# 360_led_stick_3_layer.net
KiCad netlist of a schematic drawn in EAGLE
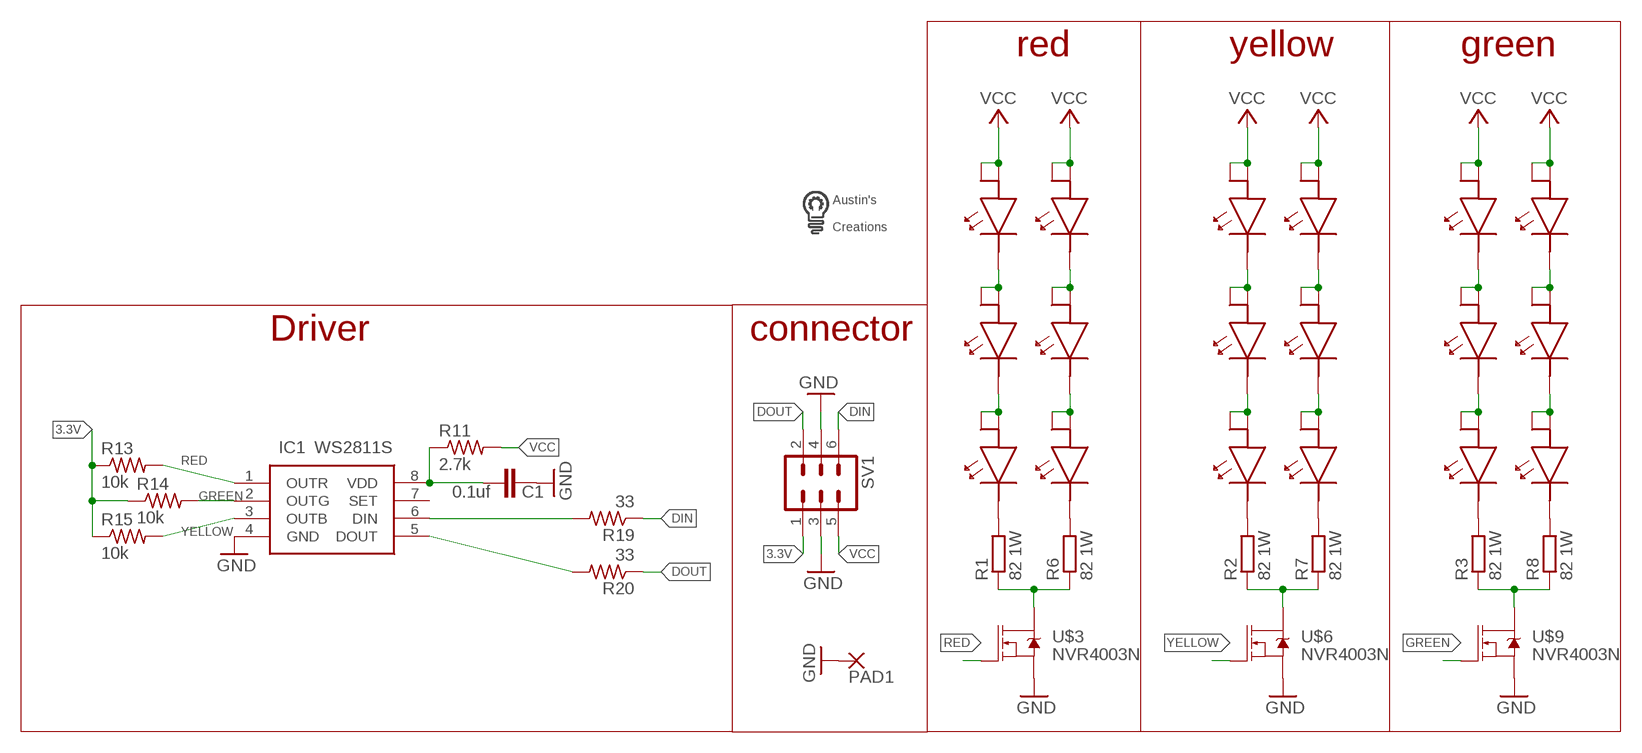
[diagram p0: schematic, sheet 1]

(export (version "E")
  (design (tool "Eeschema 10.0.6"))
  (components
    (comp (ref "C1")
      (value "0.1uf")
      (footprint "eagle-import:C0603K")
      (libsource (lib "eagle-import") (part "C-EUC0603K"))
    )
    (comp (ref "IC1")
      (value "WS2811S")
      (footprint "eagle-import:SOIC127P600X175-8N")
      (fields (field (name "MANUFACTURER_PART_NUMBER") "ws2811s"))
      (libsource (lib "eagle-import") (part "WS2811S"))
    )
    (comp (ref "PAD1")
      (value "WIREPADSMD1,27-254")
      (footprint "eagle-import:SMD1,27-2,54")
      (libsource (lib "eagle-import") (part "WIREPADSMD1,27-254"))
    )
    (comp (ref "R1")
      (value "82 1W")
      (footprint "eagle-import:R1210")
      (libsource (lib "eagle-import") (part "R-EU_R1210"))
    )
    (comp (ref "R2")
      (value "82 1W")
      (footprint "eagle-import:R1210")
      (libsource (lib "eagle-import") (part "R-EU_R1210"))
    )
    (comp (ref "R3")
      (value "82 1W")
      (footprint "eagle-import:R1210")
      (libsource (lib "eagle-import") (part "R-EU_R1210"))
    )
    (comp (ref "R6")
      (value "82 1W")
      (footprint "eagle-import:R1210")
      (libsource (lib "eagle-import") (part "R-EU_R1210"))
    )
    (comp (ref "R7")
      (value "82 1W")
      (footprint "eagle-import:R1210")
      (libsource (lib "eagle-import") (part "R-EU_R1210"))
    )
    (comp (ref "R8")
      (value "82 1W")
      (footprint "eagle-import:R1210")
      (libsource (lib "eagle-import") (part "R-EU_R1210"))
    )
    (comp (ref "R11")
      (value "2.7k")
      (footprint "eagle-import:R0603")
      (libsource (lib "eagle-import") (part "R-US_R0603"))
    )
    (comp (ref "R13")
      (value "10k")
      (footprint "eagle-import:R0603")
      (libsource (lib "eagle-import") (part "R-US_R0603"))
    )
    (comp (ref "R14")
      (value "10k")
      (footprint "eagle-import:R0603")
      (libsource (lib "eagle-import") (part "R-US_R0603"))
    )
    (comp (ref "R15")
      (value "10k")
      (footprint "eagle-import:R0603")
      (libsource (lib "eagle-import") (part "R-US_R0603"))
    )
    (comp (ref "R19")
      (value "33")
      (footprint "eagle-import:R0603")
      (libsource (lib "eagle-import") (part "R-US_R0603"))
    )
    (comp (ref "R20")
      (value "33")
      (footprint "eagle-import:R0603")
      (libsource (lib "eagle-import") (part "R-US_R0603"))
    )
    (comp (ref "SV1")
      (value "MA03-2")
      (footprint "eagle-import:MA03-2")
      (libsource (lib "eagle-import") (part "MA03-2"))
    )
    (comp (ref "U$1")
      (value "5730LED")
      (footprint "eagle-import:5730LED")
      (libsource (lib "eagle-import") (part "5730LED"))
    )
    (comp (ref "U$2")
      (value "5730LED")
      (footprint "eagle-import:5730LED")
      (libsource (lib "eagle-import") (part "5730LED"))
    )
    (comp (ref "U$3")
      (value "NVR4003N")
      (footprint "eagle-import:SOT23")
      (libsource (lib "eagle-import") (part "NVR4003N"))
    )
    (comp (ref "U$4")
      (value "5730LED")
      (footprint "eagle-import:5730LED")
      (libsource (lib "eagle-import") (part "5730LED"))
    )
    (comp (ref "U$5")
      (value "5730LED")
      (footprint "eagle-import:5730LED")
      (libsource (lib "eagle-import") (part "5730LED"))
    )
    (comp (ref "U$6")
      (value "NVR4003N")
      (footprint "eagle-import:SOT23")
      (libsource (lib "eagle-import") (part "NVR4003N"))
    )
    (comp (ref "U$7")
      (value "5730LED")
      (footprint "eagle-import:5730LED")
      (libsource (lib "eagle-import") (part "5730LED"))
    )
    (comp (ref "U$8")
      (value "5730LED")
      (footprint "eagle-import:5730LED")
      (libsource (lib "eagle-import") (part "5730LED"))
    )
    (comp (ref "U$9")
      (value "NVR4003N")
      (footprint "eagle-import:SOT23")
      (libsource (lib "eagle-import") (part "NVR4003N"))
    )
    (comp (ref "U$10")
      (value "5730LED")
      (footprint "eagle-import:5730LED")
      (libsource (lib "eagle-import") (part "5730LED"))
    )
    (comp (ref "U$11")
      (value "5730LED")
      (footprint "eagle-import:5730LED")
      (libsource (lib "eagle-import") (part "5730LED"))
    )
    (comp (ref "U$13")
      (value "5730LED")
      (footprint "eagle-import:5730LED")
      (libsource (lib "eagle-import") (part "5730LED"))
    )
    (comp (ref "U$21")
      (value "LOGO")
      (footprint "eagle-import:LOGO")
      (libsource (lib "eagle-import") (part "LOGO"))
    )
    (comp (ref "U$22")
      (value "5730LED")
      (footprint "eagle-import:5730LED")
      (libsource (lib "eagle-import") (part "5730LED"))
    )
    (comp (ref "U$23")
      (value "5730LED")
      (footprint "eagle-import:5730LED")
      (libsource (lib "eagle-import") (part "5730LED"))
    )
    (comp (ref "U$24")
      (value "5730LED")
      (footprint "eagle-import:5730LED")
      (libsource (lib "eagle-import") (part "5730LED"))
    )
    (comp (ref "U$25")
      (value "5730LED")
      (footprint "eagle-import:5730LED")
      (libsource (lib "eagle-import") (part "5730LED"))
    )
    (comp (ref "U$26")
      (value "5730LED")
      (footprint "eagle-import:5730LED")
      (libsource (lib "eagle-import") (part "5730LED"))
    )
    (comp (ref "U$27")
      (value "5730LED")
      (footprint "eagle-import:5730LED")
      (libsource (lib "eagle-import") (part "5730LED"))
    )
    (comp (ref "U$28")
      (value "5730LED")
      (footprint "eagle-import:5730LED")
      (libsource (lib "eagle-import") (part "5730LED"))
    )
    (comp (ref "U$29")
      (value "5730LED")
      (footprint "eagle-import:5730LED")
      (libsource (lib "eagle-import") (part "5730LED"))
    )
    (comp (ref "U$30")
      (value "5730LED")
      (footprint "eagle-import:5730LED")
      (libsource (lib "eagle-import") (part "5730LED"))
    )
  )
  (nets
    (net (code "1") (name "3.3V") (class "Default")
      (node (ref "R13") (pin "1") (pinfunction "1_1") (pintype "passive"))
      (node (ref "R14") (pin "1") (pinfunction "1_1") (pintype "passive"))
      (node (ref "R15") (pin "1") (pinfunction "1_1") (pintype "passive"))
      (node (ref "SV1") (pin "1") (pinfunction "1_1") (pintype "passive"))
    )
    (net (code "2") (name "DIN") (class "Default")
      (node (ref "R19") (pin "1") (pinfunction "1_1") (pintype "passive"))
      (node (ref "SV1") (pin "6") (pinfunction "6_6") (pintype "passive"))
    )
    (net (code "3") (name "DOUT") (class "Default")
      (node (ref "R20") (pin "1") (pinfunction "1_1") (pintype "passive"))
      (node (ref "SV1") (pin "2") (pinfunction "2_2") (pintype "passive"))
    )
    (net (code "4") (name "GND") (class "Default")
      (node (ref "C1") (pin "1") (pinfunction "1_1") (pintype "passive"))
      (node (ref "IC1") (pin "4") (pinfunction "GND_4") (pintype "power_in"))
      (node (ref "PAD1") (pin "1") (pinfunction "P_1") (pintype "passive"))
      (node (ref "SV1") (pin "3") (pinfunction "3_3") (pintype "passive"))
      (node (ref "SV1") (pin "4") (pinfunction "4_4") (pintype "passive"))
      (node (ref "U$3") (pin "3") (pinfunction "S_3") (pintype "bidirectional"))
      (node (ref "U$6") (pin "3") (pinfunction "S_3") (pintype "bidirectional"))
      (node (ref "U$9") (pin "3") (pinfunction "S_3") (pintype "bidirectional"))
    )
    (net (code "5") (name "GREEN") (class "Default")
      (node (ref "IC1") (pin "2") (pinfunction "OUTG_2") (pintype "output"))
      (node (ref "R14") (pin "2") (pinfunction "2_2") (pintype "passive"))
      (node (ref "U$9") (pin "2") (pinfunction "G_2") (pintype "bidirectional"))
    )
    (net (code "6") (name "Net-(IC1-DIN)") (class "Default")
      (node (ref "IC1") (pin "6") (pinfunction "DIN_6") (pintype "input"))
      (node (ref "R19") (pin "2") (pinfunction "2_2") (pintype "passive"))
    )
    (net (code "7") (name "Net-(IC1-DOUT)") (class "Default")
      (node (ref "IC1") (pin "5") (pinfunction "DOUT_5") (pintype "bidirectional"))
      (node (ref "R20") (pin "2") (pinfunction "2_2") (pintype "passive"))
    )
    (net (code "8") (name "Net-(IC1-VDD)") (class "Default")
      (node (ref "C1") (pin "2") (pinfunction "2_2") (pintype "passive"))
      (node (ref "IC1") (pin "8") (pinfunction "VDD_8") (pintype "power_in"))
      (node (ref "R11") (pin "1") (pinfunction "1_1") (pintype "passive"))
    )
    (net (code "9") (name "Net-(R1-Pad2)") (class "Default")
      (node (ref "R1") (pin "2") (pinfunction "2_2") (pintype "passive"))
      (node (ref "U$4") (pin "P$2") (pinfunction "P$2_P$2") (pintype "bidirectional"))
    )
    (net (code "10") (name "Net-(R2-Pad2)") (class "Default")
      (node (ref "R2") (pin "2") (pinfunction "2_2") (pintype "passive"))
      (node (ref "U$8") (pin "P$2") (pinfunction "P$2_P$2") (pintype "bidirectional"))
    )
    (net (code "11") (name "Net-(R3-Pad2)") (class "Default")
      (node (ref "R3") (pin "2") (pinfunction "2_2") (pintype "passive"))
      (node (ref "U$13") (pin "P$2") (pinfunction "P$2_P$2") (pintype "bidirectional"))
    )
    (net (code "12") (name "Net-(R6-Pad2)") (class "Default")
      (node (ref "R6") (pin "2") (pinfunction "2_2") (pintype "passive"))
      (node (ref "U$24") (pin "P$2") (pinfunction "P$2_P$2") (pintype "bidirectional"))
    )
    (net (code "13") (name "Net-(R7-Pad2)") (class "Default")
      (node (ref "R7") (pin "2") (pinfunction "2_2") (pintype "passive"))
      (node (ref "U$27") (pin "P$2") (pinfunction "P$2_P$2") (pintype "bidirectional"))
    )
    (net (code "14") (name "Net-(R8-Pad2)") (class "Default")
      (node (ref "R8") (pin "2") (pinfunction "2_2") (pintype "passive"))
      (node (ref "U$30") (pin "P$2") (pinfunction "P$2_P$2") (pintype "bidirectional"))
    )
    (net (code "15") (name "Net-(U$1-PadP$2)") (class "Default")
      (node (ref "U$1") (pin "P$2") (pinfunction "P$2_P$2") (pintype "bidirectional"))
      (node (ref "U$2") (pin "P$1") (pinfunction "P$1_P$1") (pintype "bidirectional"))
      (node (ref "U$2") (pin "P$3") (pinfunction "P$3_P$3") (pintype "bidirectional"))
    )
    (net (code "16") (name "Net-(U$2-PadP$2)") (class "Default")
      (node (ref "U$2") (pin "P$2") (pinfunction "P$2_P$2") (pintype "bidirectional"))
      (node (ref "U$4") (pin "P$1") (pinfunction "P$1_P$1") (pintype "bidirectional"))
      (node (ref "U$4") (pin "P$3") (pinfunction "P$3_P$3") (pintype "bidirectional"))
    )
    (net (code "17") (name "Net-(U$3-D)") (class "Default")
      (node (ref "R1") (pin "1") (pinfunction "1_1") (pintype "passive"))
      (node (ref "R6") (pin "1") (pinfunction "1_1") (pintype "passive"))
      (node (ref "U$3") (pin "1") (pinfunction "D_1") (pintype "bidirectional"))
    )
    (net (code "18") (name "Net-(U$5-PadP$2)") (class "Default")
      (node (ref "U$5") (pin "P$2") (pinfunction "P$2_P$2") (pintype "bidirectional"))
      (node (ref "U$7") (pin "P$1") (pinfunction "P$1_P$1") (pintype "bidirectional"))
      (node (ref "U$7") (pin "P$3") (pinfunction "P$3_P$3") (pintype "bidirectional"))
    )
    (net (code "19") (name "Net-(U$6-D)") (class "Default")
      (node (ref "R2") (pin "1") (pinfunction "1_1") (pintype "passive"))
      (node (ref "R7") (pin "1") (pinfunction "1_1") (pintype "passive"))
      (node (ref "U$6") (pin "1") (pinfunction "D_1") (pintype "bidirectional"))
    )
    (net (code "20") (name "Net-(U$7-PadP$2)") (class "Default")
      (node (ref "U$7") (pin "P$2") (pinfunction "P$2_P$2") (pintype "bidirectional"))
      (node (ref "U$8") (pin "P$1") (pinfunction "P$1_P$1") (pintype "bidirectional"))
      (node (ref "U$8") (pin "P$3") (pinfunction "P$3_P$3") (pintype "bidirectional"))
    )
    (net (code "21") (name "Net-(U$9-D)") (class "Default")
      (node (ref "R3") (pin "1") (pinfunction "1_1") (pintype "passive"))
      (node (ref "R8") (pin "1") (pinfunction "1_1") (pintype "passive"))
      (node (ref "U$9") (pin "1") (pinfunction "D_1") (pintype "bidirectional"))
    )
    (net (code "22") (name "Net-(U$10-PadP$2)") (class "Default")
      (node (ref "U$10") (pin "P$2") (pinfunction "P$2_P$2") (pintype "bidirectional"))
      (node (ref "U$11") (pin "P$1") (pinfunction "P$1_P$1") (pintype "bidirectional"))
      (node (ref "U$11") (pin "P$3") (pinfunction "P$3_P$3") (pintype "bidirectional"))
    )
    (net (code "23") (name "Net-(U$11-PadP$2)") (class "Default")
      (node (ref "U$11") (pin "P$2") (pinfunction "P$2_P$2") (pintype "bidirectional"))
      (node (ref "U$13") (pin "P$1") (pinfunction "P$1_P$1") (pintype "bidirectional"))
      (node (ref "U$13") (pin "P$3") (pinfunction "P$3_P$3") (pintype "bidirectional"))
    )
    (net (code "24") (name "Net-(U$22-PadP$2)") (class "Default")
      (node (ref "U$22") (pin "P$2") (pinfunction "P$2_P$2") (pintype "bidirectional"))
      (node (ref "U$23") (pin "P$1") (pinfunction "P$1_P$1") (pintype "bidirectional"))
      (node (ref "U$23") (pin "P$3") (pinfunction "P$3_P$3") (pintype "bidirectional"))
    )
    (net (code "25") (name "Net-(U$23-PadP$2)") (class "Default")
      (node (ref "U$23") (pin "P$2") (pinfunction "P$2_P$2") (pintype "bidirectional"))
      (node (ref "U$24") (pin "P$1") (pinfunction "P$1_P$1") (pintype "bidirectional"))
      (node (ref "U$24") (pin "P$3") (pinfunction "P$3_P$3") (pintype "bidirectional"))
    )
    (net (code "26") (name "Net-(U$25-PadP$2)") (class "Default")
      (node (ref "U$25") (pin "P$2") (pinfunction "P$2_P$2") (pintype "bidirectional"))
      (node (ref "U$26") (pin "P$1") (pinfunction "P$1_P$1") (pintype "bidirectional"))
      (node (ref "U$26") (pin "P$3") (pinfunction "P$3_P$3") (pintype "bidirectional"))
    )
    (net (code "27") (name "Net-(U$26-PadP$2)") (class "Default")
      (node (ref "U$26") (pin "P$2") (pinfunction "P$2_P$2") (pintype "bidirectional"))
      (node (ref "U$27") (pin "P$1") (pinfunction "P$1_P$1") (pintype "bidirectional"))
      (node (ref "U$27") (pin "P$3") (pinfunction "P$3_P$3") (pintype "bidirectional"))
    )
    (net (code "28") (name "Net-(U$28-PadP$2)") (class "Default")
      (node (ref "U$28") (pin "P$2") (pinfunction "P$2_P$2") (pintype "bidirectional"))
      (node (ref "U$29") (pin "P$1") (pinfunction "P$1_P$1") (pintype "bidirectional"))
      (node (ref "U$29") (pin "P$3") (pinfunction "P$3_P$3") (pintype "bidirectional"))
    )
    (net (code "29") (name "Net-(U$29-PadP$2)") (class "Default")
      (node (ref "U$29") (pin "P$2") (pinfunction "P$2_P$2") (pintype "bidirectional"))
      (node (ref "U$30") (pin "P$1") (pinfunction "P$1_P$1") (pintype "bidirectional"))
      (node (ref "U$30") (pin "P$3") (pinfunction "P$3_P$3") (pintype "bidirectional"))
    )
    (net (code "30") (name "RED") (class "Default")
      (node (ref "IC1") (pin "1") (pinfunction "OUTR_1") (pintype "output"))
      (node (ref "R13") (pin "2") (pinfunction "2_2") (pintype "passive"))
      (node (ref "U$3") (pin "2") (pinfunction "G_2") (pintype "bidirectional"))
    )
    (net (code "31") (name "VCC") (class "Default")
      (node (ref "R11") (pin "2") (pinfunction "2_2") (pintype "passive"))
      (node (ref "SV1") (pin "5") (pinfunction "5_5") (pintype "passive"))
      (node (ref "U$1") (pin "P$1") (pinfunction "P$1_P$1") (pintype "bidirectional"))
      (node (ref "U$1") (pin "P$3") (pinfunction "P$3_P$3") (pintype "bidirectional"))
      (node (ref "U$10") (pin "P$1") (pinfunction "P$1_P$1") (pintype "bidirectional"))
      (node (ref "U$10") (pin "P$3") (pinfunction "P$3_P$3") (pintype "bidirectional"))
      (node (ref "U$22") (pin "P$1") (pinfunction "P$1_P$1") (pintype "bidirectional"))
      (node (ref "U$22") (pin "P$3") (pinfunction "P$3_P$3") (pintype "bidirectional"))
      (node (ref "U$25") (pin "P$1") (pinfunction "P$1_P$1") (pintype "bidirectional"))
      (node (ref "U$25") (pin "P$3") (pinfunction "P$3_P$3") (pintype "bidirectional"))
      (node (ref "U$28") (pin "P$1") (pinfunction "P$1_P$1") (pintype "bidirectional"))
      (node (ref "U$28") (pin "P$3") (pinfunction "P$3_P$3") (pintype "bidirectional"))
      (node (ref "U$5") (pin "P$1") (pinfunction "P$1_P$1") (pintype "bidirectional"))
      (node (ref "U$5") (pin "P$3") (pinfunction "P$3_P$3") (pintype "bidirectional"))
    )
    (net (code "32") (name "YELLOW") (class "Default")
      (node (ref "IC1") (pin "3") (pinfunction "OUTB_3") (pintype "output"))
      (node (ref "R15") (pin "2") (pinfunction "2_2") (pintype "passive"))
      (node (ref "U$6") (pin "2") (pinfunction "G_2") (pintype "bidirectional"))
    )
    (net (code "33") (name "unconnected-(IC1-SET-Pad7)") (class "Default")
      (node (ref "IC1") (pin "7") (pinfunction "SET_7") (pintype "input"))
    )
  )
)
